# stF6.net
KiCad netlist of a schematic drawn in Altium Designer
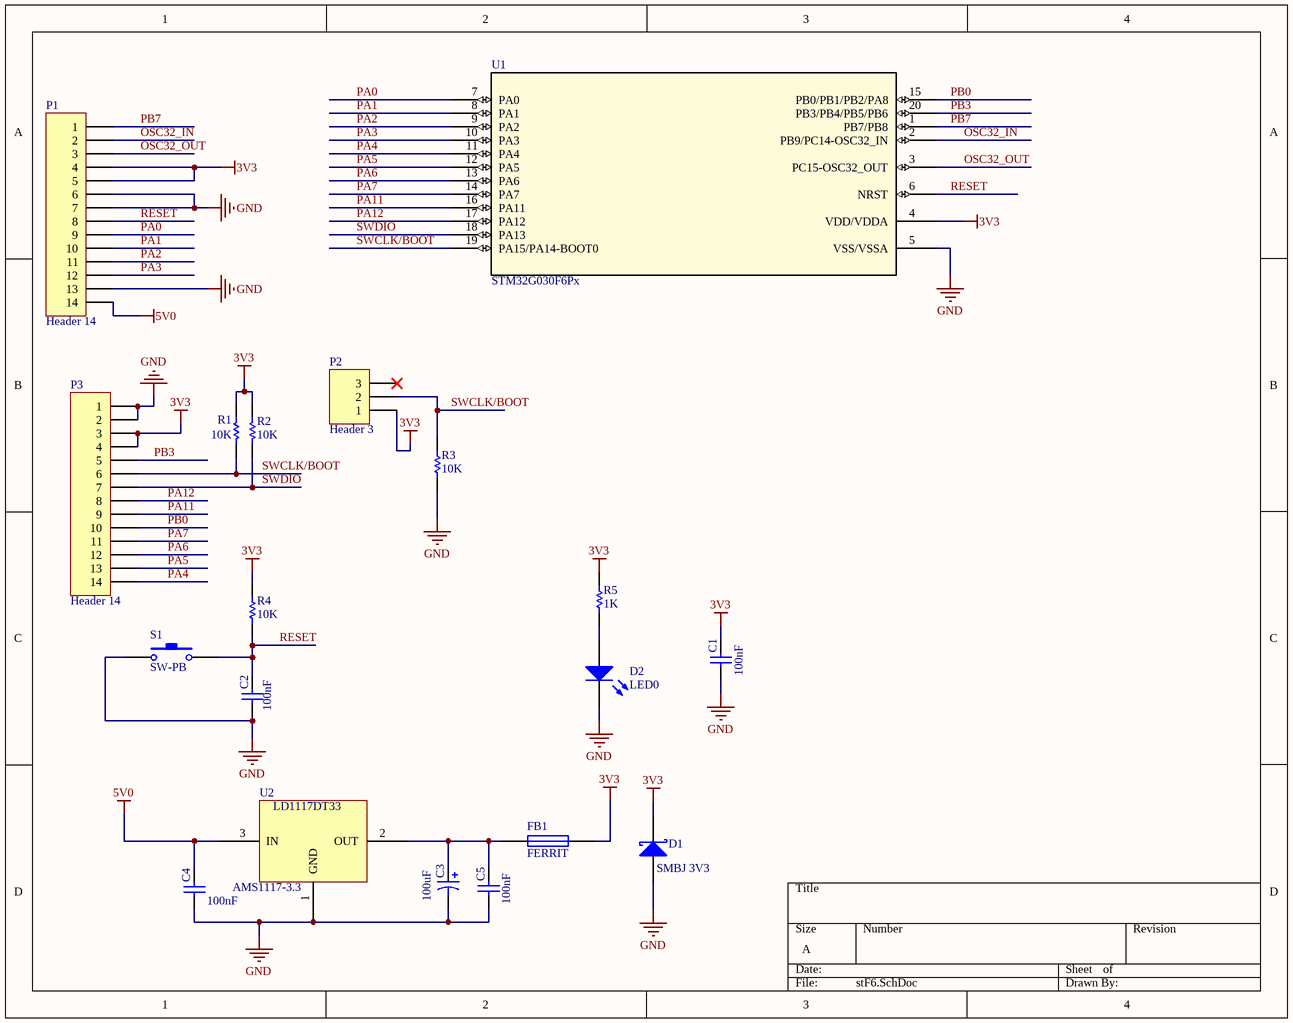
[diagram p0: stF6.SchDoc]

(export (version "E")
  (design (tool "Eeschema 10.0.6"))
  (components
    (comp (ref "C1")
      (value "100nF")
      (footprint "SMD_805")
      (description "Capacitor")
      (fields (field (name "PUBLISHER") "Altium Limited"))
      (libsource (lib "Miscellaneous Devices") (part "Cap"))
    )
    (comp (ref "C2")
      (value "100nF")
      (footprint "SMD_805")
      (description "Capacitor")
      (fields (field (name "PUBLISHER") "Altium Limited"))
      (libsource (lib "Miscellaneous Devices") (part "Cap"))
    )
    (comp (ref "C3")
      (value "100uF")
      (footprint "CAP_SMD_D")
      (description "Polarized Capacitor (Radial)")
      (fields (field (name "PUBLISHER") "Altium Limited"))
      (libsource (lib "Miscellaneous Devices") (part "Cap Pol1"))
    )
    (comp (ref "C4")
      (value "100nF")
      (footprint "SMD_805")
      (description "Capacitor")
      (fields (field (name "PUBLISHER") "Altium Limited"))
      (libsource (lib "Miscellaneous Devices") (part "Cap"))
    )
    (comp (ref "C5")
      (value "100nF")
      (footprint "SMD_805")
      (description "Capacitor")
      (fields (field (name "PUBLISHER") "Altium Limited"))
      (libsource (lib "Miscellaneous Devices") (part "Cap"))
    )
    (comp (ref "D1")
      (value "SMBJ 3V3")
      (footprint "tvs")
      (description "Schottky Rectifier")
      (fields (field (name "PUBLISHER") "Altium Limited"))
      (libsource (lib "Miscellaneous Devices") (part "Diode 11DQ03"))
    )
    (comp (ref "D2")
      (value "LED0")
      (footprint "SMD_805")
      (description "Typical INFRARED GaAs LED")
      (fields (field (name "PUBLISHER") "Altium Limited"))
      (libsource (lib "Miscellaneous Devices") (part "LED0"))
    )
    (comp (ref "FB1")
      (value "FERRIT")
      (footprint "SMD_805")
      (description "Fuse")
      (fields (field (name "PUBLISHER") "Altium Limited"))
      (libsource (lib "Miscellaneous Devices") (part "Fuse 1"))
    )
    (comp (ref "P1")
      (value "Header 14")
      (footprint "HDR1X14")
      (description "Header, 14-Pin")
      (fields (field (name "PUBLISHER") "Altium Limited"))
      (libsource (lib "Miscellaneous Connectors") (part "Header 14"))
    )
    (comp (ref "P2")
      (value "Header 3")
      (footprint "HDR1X3")
      (description "Header, 3-Pin")
      (fields (field (name "PUBLISHER") "Altium Limited"))
      (libsource (lib "Miscellaneous Connectors") (part "Header 3"))
    )
    (comp (ref "P3")
      (value "Header 14")
      (footprint "HDR1X14")
      (description "Header, 14-Pin")
      (fields (field (name "PUBLISHER") "Altium Limited"))
      (libsource (lib "Miscellaneous Connectors") (part "Header 14"))
    )
    (comp (ref "R1")
      (value "10K")
      (footprint "SMD_805")
      (description "Resistor")
      (fields (field (name "PUBLISHER") "Altium Limited"))
      (libsource (lib "Miscellaneous Devices") (part "Res1"))
    )
    (comp (ref "R2")
      (value "10K")
      (footprint "SMD_805")
      (description "Resistor")
      (fields (field (name "PUBLISHER") "Altium Limited"))
      (libsource (lib "Miscellaneous Devices") (part "Res1"))
    )
    (comp (ref "R3")
      (value "10K")
      (footprint "SMD_805")
      (description "Resistor")
      (fields (field (name "PUBLISHER") "Altium Limited"))
      (libsource (lib "Miscellaneous Devices") (part "Res1"))
    )
    (comp (ref "R4")
      (value "10K")
      (footprint "SMD_805")
      (description "Resistor")
      (fields (field (name "PUBLISHER") "Altium Limited"))
      (libsource (lib "Miscellaneous Devices") (part "Res1"))
    )
    (comp (ref "R5")
      (value "1K")
      (footprint "SMD_805")
      (description "Resistor")
      (fields (field (name "PUBLISHER") "Altium Limited"))
      (libsource (lib "Miscellaneous Devices") (part "Res1"))
    )
    (comp (ref "S1")
      (value "SW-PB")
      (footprint "smd_button")
      (description "Switch")
      (fields (field (name "PUBLISHER") "Altium Limited"))
      (libsource (lib "Miscellaneous Devices") (part "SW-PB"))
    )
    (comp (ref "U1")
      (value "STM32G030F6Px")
      (footprint "TSSOP20")
      (fields
        (field (name "MANUFACTURER_PART_NUMBER") "stm32g0_tssop20_t1")
        (field (name "COPYRIGHT") "Copyright (C) 2018 Accelerated Designs. All rights reserved")
      )
      (libsource (lib "ST Microelectronics STM32 G0") (part "STM32G030F6Px"))
    )
    (comp (ref "U2")
      (value "AMS1117-3.3")
      (footprint "SOT223")
      (libsource (lib "LD1117DT33") (part "LD1117DT33"))
    )
  )
  (nets
    (net (code "1") (name "/OSC32_IN") (class "Default")
      (node (ref "P1") (pin "2") (pinfunction "2_2") (pintype "passive"))
      (node (ref "U1") (pin "2") (pinfunction "PB9/PC14-OSC32_IN_2") (pintype "bidirectional"))
    )
    (net (code "2") (name "/OSC32_OUT") (class "Default")
      (node (ref "P1") (pin "3") (pinfunction "3_3") (pintype "passive"))
      (node (ref "U1") (pin "3") (pinfunction "PC15-OSC32_OUT_3") (pintype "bidirectional"))
    )
    (net (code "3") (name "/PA0") (class "Default")
      (node (ref "P1") (pin "9") (pinfunction "9_9") (pintype "passive"))
      (node (ref "U1") (pin "7") (pinfunction "PA0_7") (pintype "bidirectional"))
    )
    (net (code "4") (name "/PA1") (class "Default")
      (node (ref "P1") (pin "10") (pinfunction "10_10") (pintype "passive"))
      (node (ref "U1") (pin "8") (pinfunction "PA1_8") (pintype "bidirectional"))
    )
    (net (code "5") (name "/PA2") (class "Default")
      (node (ref "P1") (pin "11") (pinfunction "11_11") (pintype "passive"))
      (node (ref "U1") (pin "9") (pinfunction "PA2_9") (pintype "bidirectional"))
    )
    (net (code "6") (name "/PA3") (class "Default")
      (node (ref "P1") (pin "12") (pinfunction "12_12") (pintype "passive"))
      (node (ref "U1") (pin "10") (pinfunction "PA3_10") (pintype "bidirectional"))
    )
    (net (code "7") (name "/PA4") (class "Default")
      (node (ref "P3") (pin "14") (pinfunction "14_14") (pintype "passive"))
      (node (ref "U1") (pin "11") (pinfunction "PA4_11") (pintype "bidirectional"))
    )
    (net (code "8") (name "/PA5") (class "Default")
      (node (ref "P3") (pin "13") (pinfunction "13_13") (pintype "passive"))
      (node (ref "U1") (pin "12") (pinfunction "PA5_12") (pintype "bidirectional"))
    )
    (net (code "9") (name "/PA6") (class "Default")
      (node (ref "P3") (pin "12") (pinfunction "12_12") (pintype "passive"))
      (node (ref "U1") (pin "13") (pinfunction "PA6_13") (pintype "bidirectional"))
    )
    (net (code "10") (name "/PA7") (class "Default")
      (node (ref "P3") (pin "11") (pinfunction "11_11") (pintype "passive"))
      (node (ref "U1") (pin "14") (pinfunction "PA7_14") (pintype "bidirectional"))
    )
    (net (code "11") (name "/PA11") (class "Default")
      (node (ref "P3") (pin "9") (pinfunction "9_9") (pintype "passive"))
      (node (ref "U1") (pin "16") (pinfunction "PA11_16") (pintype "bidirectional"))
    )
    (net (code "12") (name "/PA12") (class "Default")
      (node (ref "P3") (pin "8") (pinfunction "8_8") (pintype "passive"))
      (node (ref "U1") (pin "17") (pinfunction "PA12_17") (pintype "bidirectional"))
    )
    (net (code "13") (name "/PB0") (class "Default")
      (node (ref "P3") (pin "10") (pinfunction "10_10") (pintype "passive"))
      (node (ref "U1") (pin "15") (pinfunction "PB0/PB1/PB2/PA8_15") (pintype "bidirectional"))
    )
    (net (code "14") (name "/PB3") (class "Default")
      (node (ref "P3") (pin "5") (pinfunction "5_5") (pintype "passive"))
      (node (ref "U1") (pin "20") (pinfunction "PB3/PB4/PB5/PB6_20") (pintype "bidirectional"))
    )
    (net (code "15") (name "/PB7") (class "Default")
      (node (ref "P1") (pin "1") (pinfunction "1_1") (pintype "passive"))
      (node (ref "U1") (pin "1") (pinfunction "PB7/PB8_1") (pintype "bidirectional"))
    )
    (net (code "16") (name "/RESET") (class "Default")
      (node (ref "C2") (pin "2") (pinfunction "2_2") (pintype "passive"))
      (node (ref "P1") (pin "8") (pinfunction "8_8") (pintype "passive"))
      (node (ref "R4") (pin "1") (pinfunction "1_1") (pintype "passive"))
      (node (ref "S1") (pin "2") (pinfunction "2_2") (pintype "passive"))
      (node (ref "U1") (pin "6") (pinfunction "NRST_6") (pintype "bidirectional"))
    )
    (net (code "17") (name "/SWCLK{slash}BOOT") (class "Default")
      (node (ref "P2") (pin "2") (pinfunction "2_2") (pintype "passive"))
      (node (ref "P3") (pin "6") (pinfunction "6_6") (pintype "passive"))
      (node (ref "R1") (pin "1") (pinfunction "1_1") (pintype "passive"))
      (node (ref "R3") (pin "2") (pinfunction "2_2") (pintype "passive"))
      (node (ref "U1") (pin "19") (pinfunction "PA15/PA14-BOOT0_19") (pintype "bidirectional"))
    )
    (net (code "18") (name "/SWDIO") (class "Default")
      (node (ref "P3") (pin "7") (pinfunction "7_7") (pintype "passive"))
      (node (ref "R2") (pin "1") (pinfunction "1_1") (pintype "passive"))
      (node (ref "U1") (pin "18") (pinfunction "PA13_18") (pintype "bidirectional"))
    )
    (net (code "19") (name "3V3") (class "Default")
      (node (ref "C1") (pin "2") (pinfunction "2_2") (pintype "passive"))
      (node (ref "D1") (pin "2") (pinfunction "K_2") (pintype "passive"))
      (node (ref "FB1") (pin "1") (pinfunction "1_1") (pintype "passive"))
      (node (ref "P1") (pin "4") (pinfunction "4_4") (pintype "passive"))
      (node (ref "P1") (pin "5") (pinfunction "5_5") (pintype "passive"))
      (node (ref "P2") (pin "1") (pinfunction "1_1") (pintype "passive"))
      (node (ref "P3") (pin "3") (pinfunction "3_3") (pintype "passive"))
      (node (ref "P3") (pin "4") (pinfunction "4_4") (pintype "passive"))
      (node (ref "R1") (pin "2") (pinfunction "2_2") (pintype "passive"))
      (node (ref "R2") (pin "2") (pinfunction "2_2") (pintype "passive"))
      (node (ref "R4") (pin "2") (pinfunction "2_2") (pintype "passive"))
      (node (ref "R5") (pin "2") (pinfunction "2_2") (pintype "passive"))
      (node (ref "U1") (pin "4") (pinfunction "VDD/VDDA_4") (pintype "power_in"))
    )
    (net (code "20") (name "5V0") (class "Default")
      (node (ref "C4") (pin "2") (pinfunction "2_2") (pintype "passive"))
      (node (ref "P1") (pin "14") (pinfunction "14_14") (pintype "passive"))
      (node (ref "U2") (pin "3") (pinfunction "IN_3") (pintype "passive"))
    )
    (net (code "21") (name "GND") (class "Default")
      (node (ref "C1") (pin "1") (pinfunction "1_1") (pintype "passive"))
      (node (ref "C2") (pin "1") (pinfunction "1_1") (pintype "passive"))
      (node (ref "C3") (pin "2") (pinfunction "2_2") (pintype "passive"))
      (node (ref "C4") (pin "1") (pinfunction "1_1") (pintype "passive"))
      (node (ref "C5") (pin "1") (pinfunction "1_1") (pintype "passive"))
      (node (ref "D1") (pin "1") (pinfunction "A_1") (pintype "passive"))
      (node (ref "D2") (pin "2") (pinfunction "K_2") (pintype "passive"))
      (node (ref "P1") (pin "13") (pinfunction "13_13") (pintype "passive"))
      (node (ref "P1") (pin "6") (pinfunction "6_6") (pintype "passive"))
      (node (ref "P1") (pin "7") (pinfunction "7_7") (pintype "passive"))
      (node (ref "P3") (pin "1") (pinfunction "1_1") (pintype "passive"))
      (node (ref "P3") (pin "2") (pinfunction "2_2") (pintype "passive"))
      (node (ref "R3") (pin "1") (pinfunction "1_1") (pintype "passive"))
      (node (ref "S1") (pin "1") (pinfunction "1_1") (pintype "passive"))
      (node (ref "U1") (pin "5") (pinfunction "VSS/VSSA_5") (pintype "power_in"))
      (node (ref "U2") (pin "1") (pinfunction "GND_1") (pintype "passive"))
    )
    (net (code "22") (name "Net-(D2-A)") (class "Default")
      (node (ref "D2") (pin "1") (pinfunction "A_1") (pintype "passive"))
      (node (ref "R5") (pin "1") (pinfunction "1_1") (pintype "passive"))
    )
    (net (code "23") (name "Net-(U2-OUT)") (class "Default")
      (node (ref "C3") (pin "1") (pinfunction "1_1") (pintype "passive"))
      (node (ref "C5") (pin "2") (pinfunction "2_2") (pintype "passive"))
      (node (ref "FB1") (pin "2") (pinfunction "2_2") (pintype "passive"))
      (node (ref "U2") (pin "2") (pinfunction "OUT_2") (pintype "passive"))
    )
    (net (code "24") (name "unconnected-(P2-Pad3)") (class "Default")
      (node (ref "P2") (pin "3") (pinfunction "3_3") (pintype "passive+no_connect"))
    )
  )
)
